# room1121.net
KiCad netlist of a schematic drawn in EAGLE
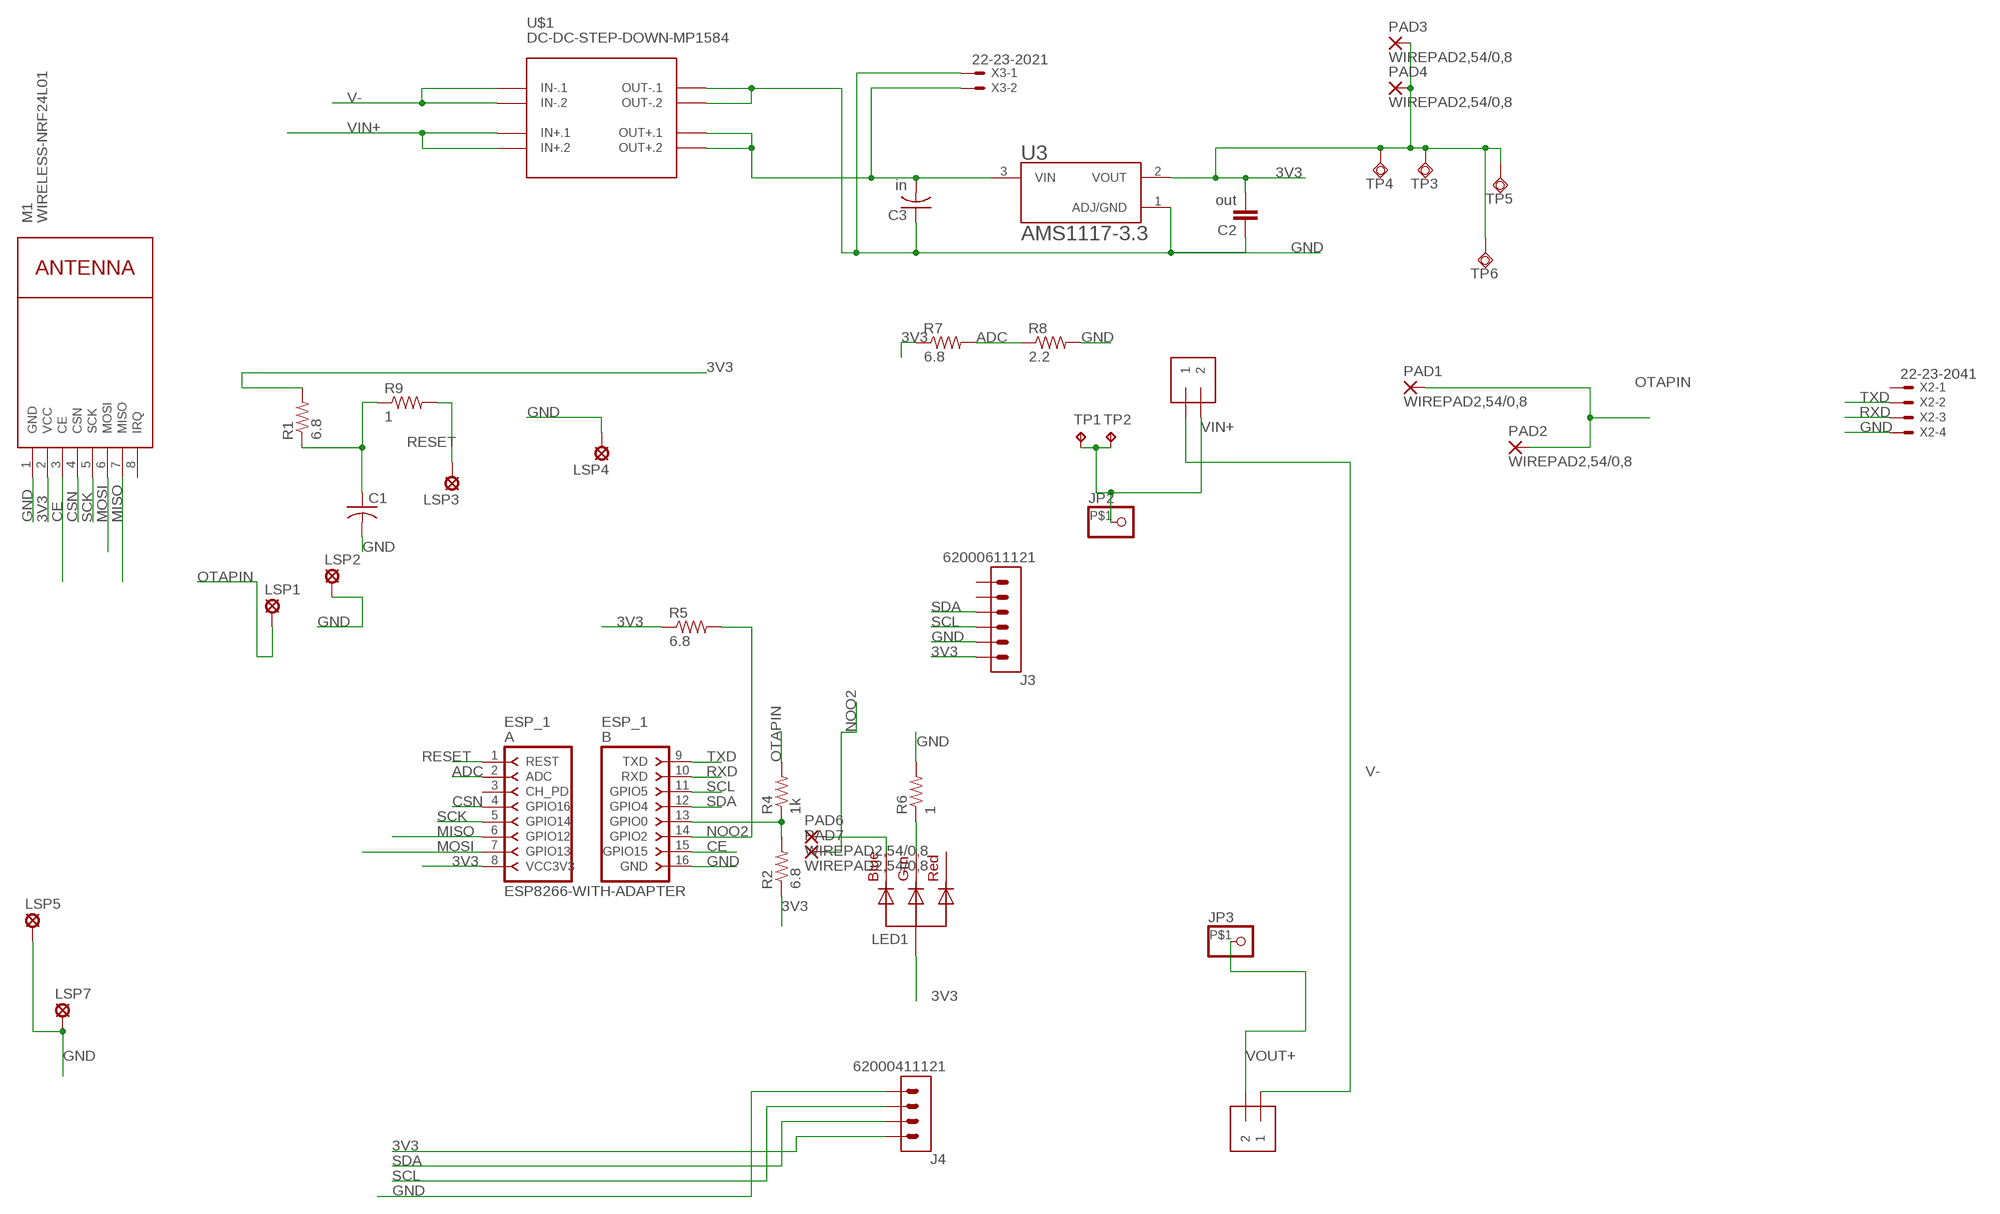
[diagram p0: schematic, sheet 1]

(export (version "E")
  (design (tool "Eeschema 10.0.6"))
  (components
    (comp (ref "C1")
      (value "C-US025-040X050")
      (footprint "eagle-import:C025-040X050")
      (libsource (lib "eagle-import") (part "C-US025-040X050"))
    )
    (comp (ref "C2")
      (value "out")
      (footprint "eagle-import:C025-060X050")
      (libsource (lib "eagle-import") (part "C-EU025-060X050"))
    )
    (comp (ref "C3")
      (value "in")
      (footprint "eagle-import:C075-032X103")
      (libsource (lib "eagle-import") (part "C-US075-032X103"))
    )
    (comp (ref "ESP_1")
      (value "ESP8266-WITH-ADAPTER")
      (footprint "eagle-import:ESP8266-ADAPTER")
      (libsource (lib "eagle-import") (part "ESP8266-WITH-ADAPTER"))
    )
    (comp (ref "J1")
      (value "1X2-3.5MM")
      (footprint "eagle-import:1X2-3.5MM")
      (libsource (lib "eagle-import") (part "1X2-3.5MM"))
    )
    (comp (ref "J2")
      (value "1X2-3.5MM")
      (footprint "eagle-import:1X2-3.5MM")
      (libsource (lib "eagle-import") (part "1X2-3.5MM"))
    )
    (comp (ref "J3")
      (value "62000611121")
      (footprint "eagle-import:62000611121")
      (fields (field (name "MANUFACTURER") "Würth Elektronik ") (field (name "CREATED_BY") "PCBLayout.com"))
      (libsource (lib "eagle-import") (part "62000611121"))
    )
    (comp (ref "J4")
      (value "62000411121")
      (footprint "eagle-import:62000411121")
      (fields (field (name "MANUFACTURER") "Würth Elektronik ") (field (name "CREATED_BY") "PCBLayout.com"))
      (libsource (lib "eagle-import") (part "62000411121"))
    )
    (comp (ref "JP2")
      (value "PINHD-1X1-BIGPOGO")
      (footprint "eagle-import:1X1-BIGPOGO")
      (libsource (lib "eagle-import") (part "PINHD-1X1-BIGPOGO"))
    )
    (comp (ref "JP3")
      (value "PINHD-1X1-BIGPOGO")
      (footprint "eagle-import:1X1-BIGPOGO")
      (libsource (lib "eagle-import") (part "PINHD-1X1-BIGPOGO"))
    )
    (comp (ref "LED1")
      (value "RGBLED_CA-5MM")
      (footprint "eagle-import:LED5MMRGB")
      (libsource (lib "eagle-import") (part "RGBLED_CA-5MM"))
    )
    (comp (ref "LSP1")
      (value "SE14")
      (footprint "eagle-import:SE14")
      (libsource (lib "eagle-import") (part "SE14"))
    )
    (comp (ref "LSP2")
      (value "SE14")
      (footprint "eagle-import:SE14")
      (libsource (lib "eagle-import") (part "SE14"))
    )
    (comp (ref "LSP3")
      (value "SE14")
      (footprint "eagle-import:SE14")
      (libsource (lib "eagle-import") (part "SE14"))
    )
    (comp (ref "LSP4")
      (value "SE14")
      (footprint "eagle-import:SE14")
      (libsource (lib "eagle-import") (part "SE14"))
    )
    (comp (ref "LSP5")
      (value "MCS10B")
      (footprint "eagle-import:MCS10B")
      (libsource (lib "eagle-import") (part "MCS10B"))
    )
    (comp (ref "LSP7")
      (value "MCS10B")
      (footprint "eagle-import:MCS10B")
      (libsource (lib "eagle-import") (part "MCS10B"))
    )
    (comp (ref "M1")
      (value "WIRELESS-NRF24L01")
      (footprint "eagle-import:WIRELESS-NRF24L01")
      (libsource (lib "eagle-import") (part "WIRELESS-NRF24L01"))
    )
    (comp (ref "PAD1")
      (value "WIREPAD2,54/0,8")
      (footprint "eagle-import:2,54_0,8")
      (libsource (lib "eagle-import") (part "WIREPAD2,54/0,8"))
    )
    (comp (ref "PAD2")
      (value "WIREPAD2,54/0,8")
      (footprint "eagle-import:2,54_0,8")
      (libsource (lib "eagle-import") (part "WIREPAD2,54/0,8"))
    )
    (comp (ref "PAD3")
      (value "WIREPAD2,54/0,8")
      (footprint "eagle-import:2,54_0,8")
      (libsource (lib "eagle-import") (part "WIREPAD2,54/0,8"))
    )
    (comp (ref "PAD4")
      (value "WIREPAD2,54/0,8")
      (footprint "eagle-import:2,54_0,8")
      (libsource (lib "eagle-import") (part "WIREPAD2,54/0,8"))
    )
    (comp (ref "PAD6")
      (value "WIREPAD2,54/0,8")
      (footprint "eagle-import:2,54_0,8")
      (libsource (lib "eagle-import") (part "WIREPAD2,54/0,8"))
    )
    (comp (ref "PAD7")
      (value "WIREPAD2,54/0,8")
      (footprint "eagle-import:2,54_0,8")
      (libsource (lib "eagle-import") (part "WIREPAD2,54/0,8"))
    )
    (comp (ref "R1")
      (value "6.8")
      (footprint "eagle-import:0207_15")
      (libsource (lib "eagle-import") (part "rCCl_R-US_0207/15"))
    )
    (comp (ref "R2")
      (value "6.8")
      (footprint "eagle-import:0207_15")
      (libsource (lib "eagle-import") (part "R-US_0207/15"))
    )
    (comp (ref "R4")
      (value "1k")
      (footprint "eagle-import:0207_15")
      (libsource (lib "eagle-import") (part "rCCl_R-US_0207/15"))
    )
    (comp (ref "R5")
      (value "6.8")
      (footprint "eagle-import:0207_12")
      (libsource (lib "eagle-import") (part "R-US_0207/12"))
    )
    (comp (ref "R6")
      (value "1")
      (footprint "eagle-import:0207_10")
      (libsource (lib "eagle-import") (part "R-US_0207/10"))
    )
    (comp (ref "R7")
      (value "6.8")
      (footprint "eagle-import:0207_12")
      (libsource (lib "eagle-import") (part "R-US_0207/12"))
    )
    (comp (ref "R8")
      (value "2.2")
      (footprint "eagle-import:0207_15")
      (libsource (lib "eagle-import") (part "rCCl_R-US_0207/15"))
    )
    (comp (ref "R9")
      (value "1")
      (footprint "eagle-import:0207_12")
      (libsource (lib "eagle-import") (part "R-US_0207/12"))
    )
    (comp (ref "TP1")
      (value "TPPAD1-20Y")
      (footprint "eagle-import:P1-20Y")
      (libsource (lib "eagle-import") (part "TPPAD1-20Y"))
    )
    (comp (ref "TP2")
      (value "TPPAD1-20Y")
      (footprint "eagle-import:P1-20Y")
      (libsource (lib "eagle-import") (part "TPPAD1-20Y"))
    )
    (comp (ref "TP3")
      (value "TPSQPAD1-13Y")
      (footprint "eagle-import:P1-13Y")
      (libsource (lib "eagle-import") (part "TPSQPAD1-13Y"))
    )
    (comp (ref "TP4")
      (value "TPSQPAD1-13Y")
      (footprint "eagle-import:P1-13Y")
      (libsource (lib "eagle-import") (part "TPSQPAD1-13Y"))
    )
    (comp (ref "TP5")
      (value "TPSQPAD1-13Y")
      (footprint "eagle-import:P1-13Y")
      (libsource (lib "eagle-import") (part "TPSQPAD1-13Y"))
    )
    (comp (ref "TP6")
      (value "TPSQPAD1-13Y")
      (footprint "eagle-import:P1-13Y")
      (libsource (lib "eagle-import") (part "TPSQPAD1-13Y"))
    )
    (comp (ref "U$1")
      (value "DC-DC-STEP-DOWN-MP1584")
      (footprint "eagle-import:DC-DC-STEP-DOWN-MP1584")
      (libsource (lib "eagle-import") (part "DC-DC-STEP-DOWN-MP1584"))
    )
    (comp (ref "U3")
      (value "AMS1117-3.3")
      (footprint "eagle-import:SOT229P700X180-4N")
      (fields (field (name "MF") "Advanced Monolithic Systems"))
      (libsource (lib "eagle-import") (part "AMS1117-3.3"))
    )
    (comp (ref "X2")
      (value "22-23-2041")
      (footprint "eagle-import:22-23-2041")
      (fields (field (name "MF") "MOLEX"))
      (libsource (lib "eagle-import") (part "22-23-2041"))
    )
    (comp (ref "X3")
      (value "22-23-2021")
      (footprint "eagle-import:22-23-2021")
      (fields (field (name "MF") "MOLEX"))
      (libsource (lib "eagle-import") (part "22-23-2021"))
    )
  )
  (nets
    (net (code "1") (name "/3V3") (class "Default")
      (node (ref "C2") (pin "2") (pinfunction "2_2") (pintype "passive"))
      (node (ref "ESP_1") (pin "8") (pinfunction "VCC3V3_8") (pintype "passive"))
      (node (ref "J3") (pin "1") (pinfunction "1_1") (pintype "passive"))
      (node (ref "J4") (pin "1") (pinfunction "1_1") (pintype "passive"))
      (node (ref "LED1") (pin "2") (pinfunction "VCC_2") (pintype "bidirectional"))
      (node (ref "M1") (pin "2") (pinfunction "VCC_2") (pintype "power_in"))
      (node (ref "PAD3") (pin "1") (pinfunction "P_1") (pintype "passive"))
      (node (ref "PAD4") (pin "1") (pinfunction "P_1") (pintype "passive"))
      (node (ref "R1") (pin "2") (pinfunction "2_2") (pintype "passive"))
      (node (ref "R2") (pin "1") (pinfunction "1_1") (pintype "passive"))
      (node (ref "R5") (pin "1") (pinfunction "1_1") (pintype "passive"))
      (node (ref "R7") (pin "1") (pinfunction "1_1") (pintype "passive"))
      (node (ref "TP3") (pin "TP") (pinfunction "TP_TP") (pintype "input"))
      (node (ref "TP4") (pin "TP") (pinfunction "TP_TP") (pintype "input"))
      (node (ref "TP5") (pin "TP") (pinfunction "TP_TP") (pintype "input"))
      (node (ref "TP6") (pin "TP") (pinfunction "TP_TP") (pintype "input"))
      (node (ref "U3") (pin "2") (pinfunction "VOUT_2") (pintype "output"))
    )
    (net (code "2") (name "/ADC") (class "Default")
      (node (ref "ESP_1") (pin "2") (pinfunction "ADC_2") (pintype "passive"))
      (node (ref "R7") (pin "2") (pinfunction "2_2") (pintype "passive"))
      (node (ref "R8") (pin "1") (pinfunction "1_1") (pintype "passive"))
    )
    (net (code "3") (name "/CE") (class "Default")
      (node (ref "ESP_1") (pin "15") (pinfunction "GPIO15_15") (pintype "passive"))
      (node (ref "M1") (pin "3") (pinfunction "CE_3") (pintype "bidirectional"))
    )
    (net (code "4") (name "/CSN") (class "Default")
      (node (ref "ESP_1") (pin "4") (pinfunction "GPIO16_4") (pintype "passive"))
      (node (ref "M1") (pin "4") (pinfunction "CSN_4") (pintype "bidirectional"))
    )
    (net (code "5") (name "/GND") (class "Default")
      (node (ref "C1") (pin "2") (pinfunction "2_2") (pintype "passive"))
      (node (ref "C2") (pin "1") (pinfunction "1_1") (pintype "passive"))
      (node (ref "C3") (pin "1") (pinfunction "1_1") (pintype "passive"))
      (node (ref "ESP_1") (pin "16") (pinfunction "GND_16") (pintype "passive"))
      (node (ref "J3") (pin "2") (pinfunction "2_2") (pintype "passive"))
      (node (ref "J4") (pin "4") (pinfunction "4_4") (pintype "passive"))
      (node (ref "LSP2") (pin "MP") (pinfunction "MP_MP") (pintype "passive"))
      (node (ref "LSP4") (pin "MP") (pinfunction "MP_MP") (pintype "passive"))
      (node (ref "LSP5") (pin "MP") (pinfunction "MP_MP") (pintype "passive"))
      (node (ref "LSP7") (pin "MP") (pinfunction "MP_MP") (pintype "passive"))
      (node (ref "M1") (pin "1") (pinfunction "GND_1") (pintype "power_in"))
      (node (ref "R6") (pin "2") (pinfunction "2_2") (pintype "passive"))
      (node (ref "R8") (pin "2") (pinfunction "2_2") (pintype "passive"))
      (node (ref "U$1") (pin "OUT-.1") (pinfunction "OUT-.1_OUT-.1") (pintype "bidirectional"))
      (node (ref "U$1") (pin "OUT-.2") (pinfunction "OUT-.2_OUT-.2") (pintype "bidirectional"))
      (node (ref "U3") (pin "1") (pinfunction "ADJ/GND_1") (pintype "power_in"))
      (node (ref "X2") (pin "4") (pinfunction "S_4") (pintype "passive"))
      (node (ref "X3") (pin "1") (pinfunction "S_1") (pintype "passive"))
    )
    (net (code "6") (name "/MISO") (class "Default")
      (node (ref "ESP_1") (pin "6") (pinfunction "GPIO12_6") (pintype "passive"))
      (node (ref "M1") (pin "7") (pinfunction "MISO_7") (pintype "bidirectional"))
    )
    (net (code "7") (name "/MOSI") (class "Default")
      (node (ref "ESP_1") (pin "7") (pinfunction "GPIO13_7") (pintype "passive"))
      (node (ref "M1") (pin "6") (pinfunction "MOSI_6") (pintype "bidirectional"))
    )
    (net (code "8") (name "/NOO2") (class "Default")
      (node (ref "ESP_1") (pin "14") (pinfunction "GPIO2_14") (pintype "passive"))
      (node (ref "PAD7") (pin "1") (pinfunction "P_1") (pintype "passive"))
      (node (ref "R5") (pin "2") (pinfunction "2_2") (pintype "passive"))
    )
    (net (code "9") (name "/OTAPIN") (class "Default")
      (node (ref "LSP1") (pin "MP") (pinfunction "MP_MP") (pintype "passive"))
      (node (ref "PAD1") (pin "1") (pinfunction "P_1") (pintype "passive"))
      (node (ref "PAD2") (pin "1") (pinfunction "P_1") (pintype "passive"))
      (node (ref "R4") (pin "2") (pinfunction "2_2") (pintype "passive"))
    )
    (net (code "10") (name "/RESET") (class "Default")
      (node (ref "C1") (pin "1") (pinfunction "1_1") (pintype "passive"))
      (node (ref "ESP_1") (pin "1") (pinfunction "REST_1") (pintype "passive"))
      (node (ref "R1") (pin "1") (pinfunction "1_1") (pintype "passive"))
      (node (ref "R9") (pin "1") (pinfunction "1_1") (pintype "passive"))
    )
    (net (code "11") (name "/RXD") (class "Default")
      (node (ref "ESP_1") (pin "10") (pinfunction "RXD_10") (pintype "passive"))
      (node (ref "X2") (pin "3") (pinfunction "S_3") (pintype "passive"))
    )
    (net (code "12") (name "/SCK") (class "Default")
      (node (ref "ESP_1") (pin "5") (pinfunction "GPIO14_5") (pintype "passive"))
      (node (ref "M1") (pin "5") (pinfunction "SCK_5") (pintype "bidirectional"))
    )
    (net (code "13") (name "/SCL") (class "Default")
      (node (ref "ESP_1") (pin "11") (pinfunction "GPIO5_11") (pintype "passive"))
      (node (ref "J3") (pin "3") (pinfunction "3_3") (pintype "passive"))
      (node (ref "J4") (pin "3") (pinfunction "3_3") (pintype "passive"))
    )
    (net (code "14") (name "/SDA") (class "Default")
      (node (ref "ESP_1") (pin "12") (pinfunction "GPIO4_12") (pintype "passive"))
      (node (ref "J3") (pin "4") (pinfunction "4_4") (pintype "passive"))
      (node (ref "J4") (pin "2") (pinfunction "2_2") (pintype "passive"))
    )
    (net (code "15") (name "/TXD") (class "Default")
      (node (ref "ESP_1") (pin "9") (pinfunction "TXD_9") (pintype "passive"))
      (node (ref "X2") (pin "2") (pinfunction "S_2") (pintype "passive"))
    )
    (net (code "16") (name "/V-") (class "Default")
      (node (ref "J1") (pin "1") (pinfunction "1_1") (pintype "passive"))
      (node (ref "J2") (pin "1") (pinfunction "1_1") (pintype "passive"))
      (node (ref "U$1") (pin "IN-.1") (pinfunction "IN-.1_IN-.1") (pintype "bidirectional"))
      (node (ref "U$1") (pin "IN-.2") (pinfunction "IN-.2_IN-.2") (pintype "bidirectional"))
    )
    (net (code "17") (name "/VIN+") (class "Default")
      (node (ref "J2") (pin "2") (pinfunction "2_2") (pintype "passive"))
      (node (ref "JP2") (pin "P$1") (pinfunction "1_P$1") (pintype "passive"))
      (node (ref "TP1") (pin "TP") (pinfunction "TP_TP") (pintype "input"))
      (node (ref "TP2") (pin "TP") (pinfunction "TP_TP") (pintype "input"))
      (node (ref "U$1") (pin "IN+.1") (pinfunction "IN+.1_IN+.1") (pintype "bidirectional"))
      (node (ref "U$1") (pin "IN+.2") (pinfunction "IN+.2_IN+.2") (pintype "bidirectional"))
    )
    (net (code "18") (name "/VOUT+") (class "Default")
      (node (ref "J1") (pin "2") (pinfunction "2_2") (pintype "passive"))
      (node (ref "JP3") (pin "P$1") (pinfunction "1_P$1") (pintype "passive"))
    )
    (net (code "19") (name "Net-(ESP_1-GPIO0)") (class "Default")
      (node (ref "ESP_1") (pin "13") (pinfunction "GPIO0_13") (pintype "passive"))
      (node (ref "R2") (pin "2") (pinfunction "2_2") (pintype "passive"))
      (node (ref "R4") (pin "1") (pinfunction "1_1") (pintype "passive"))
    )
    (net (code "20") (name "Net-(LED1-BLUE)") (class "Default")
      (node (ref "LED1") (pin "4") (pinfunction "BLUE_4") (pintype "bidirectional"))
      (node (ref "PAD6") (pin "1") (pinfunction "P_1") (pintype "passive"))
    )
    (net (code "21") (name "Net-(LED1-GREEN)") (class "Default")
      (node (ref "LED1") (pin "3") (pinfunction "GREEN_3") (pintype "bidirectional"))
      (node (ref "R6") (pin "1") (pinfunction "1_1") (pintype "passive"))
    )
    (net (code "22") (name "Net-(LSP3-PadMP)") (class "Default")
      (node (ref "LSP3") (pin "MP") (pinfunction "MP_MP") (pintype "passive"))
      (node (ref "R9") (pin "2") (pinfunction "2_2") (pintype "passive"))
    )
    (net (code "23") (name "Net-(U3-VIN)") (class "Default")
      (node (ref "C3") (pin "2") (pinfunction "2_2") (pintype "passive"))
      (node (ref "U$1") (pin "OUT+.1") (pinfunction "OUT+.1_OUT+.1") (pintype "bidirectional"))
      (node (ref "U$1") (pin "OUT+.2") (pinfunction "OUT+.2_OUT+.2") (pintype "bidirectional"))
      (node (ref "U3") (pin "3") (pinfunction "VIN_3") (pintype "input"))
      (node (ref "X3") (pin "2") (pinfunction "S_2") (pintype "passive"))
    )
    (net (code "24") (name "unconnected-(ESP_1-CH_PD-Pad3)") (class "Default")
      (node (ref "ESP_1") (pin "3") (pinfunction "CH_PD_3") (pintype "passive"))
    )
    (net (code "25") (name "unconnected-(J3-Pad5)") (class "Default")
      (node (ref "J3") (pin "5") (pinfunction "5_5") (pintype "passive"))
    )
    (net (code "26") (name "unconnected-(J3-Pad6)") (class "Default")
      (node (ref "J3") (pin "6") (pinfunction "6_6") (pintype "passive"))
    )
    (net (code "27") (name "unconnected-(LED1-RED-Pad1)") (class "Default")
      (node (ref "LED1") (pin "1") (pinfunction "RED_1") (pintype "bidirectional"))
    )
    (net (code "28") (name "unconnected-(M1-IRQ-Pad8)") (class "Default")
      (node (ref "M1") (pin "8") (pinfunction "IRQ_8") (pintype "bidirectional"))
    )
    (net (code "29") (name "unconnected-(X2A-S-Pad1)") (class "Default")
      (node (ref "X2") (pin "1") (pinfunction "S_1") (pintype "passive"))
    )
  )
)
